# Optronik.net
KiCad netlist of a schematic drawn in EAGLE
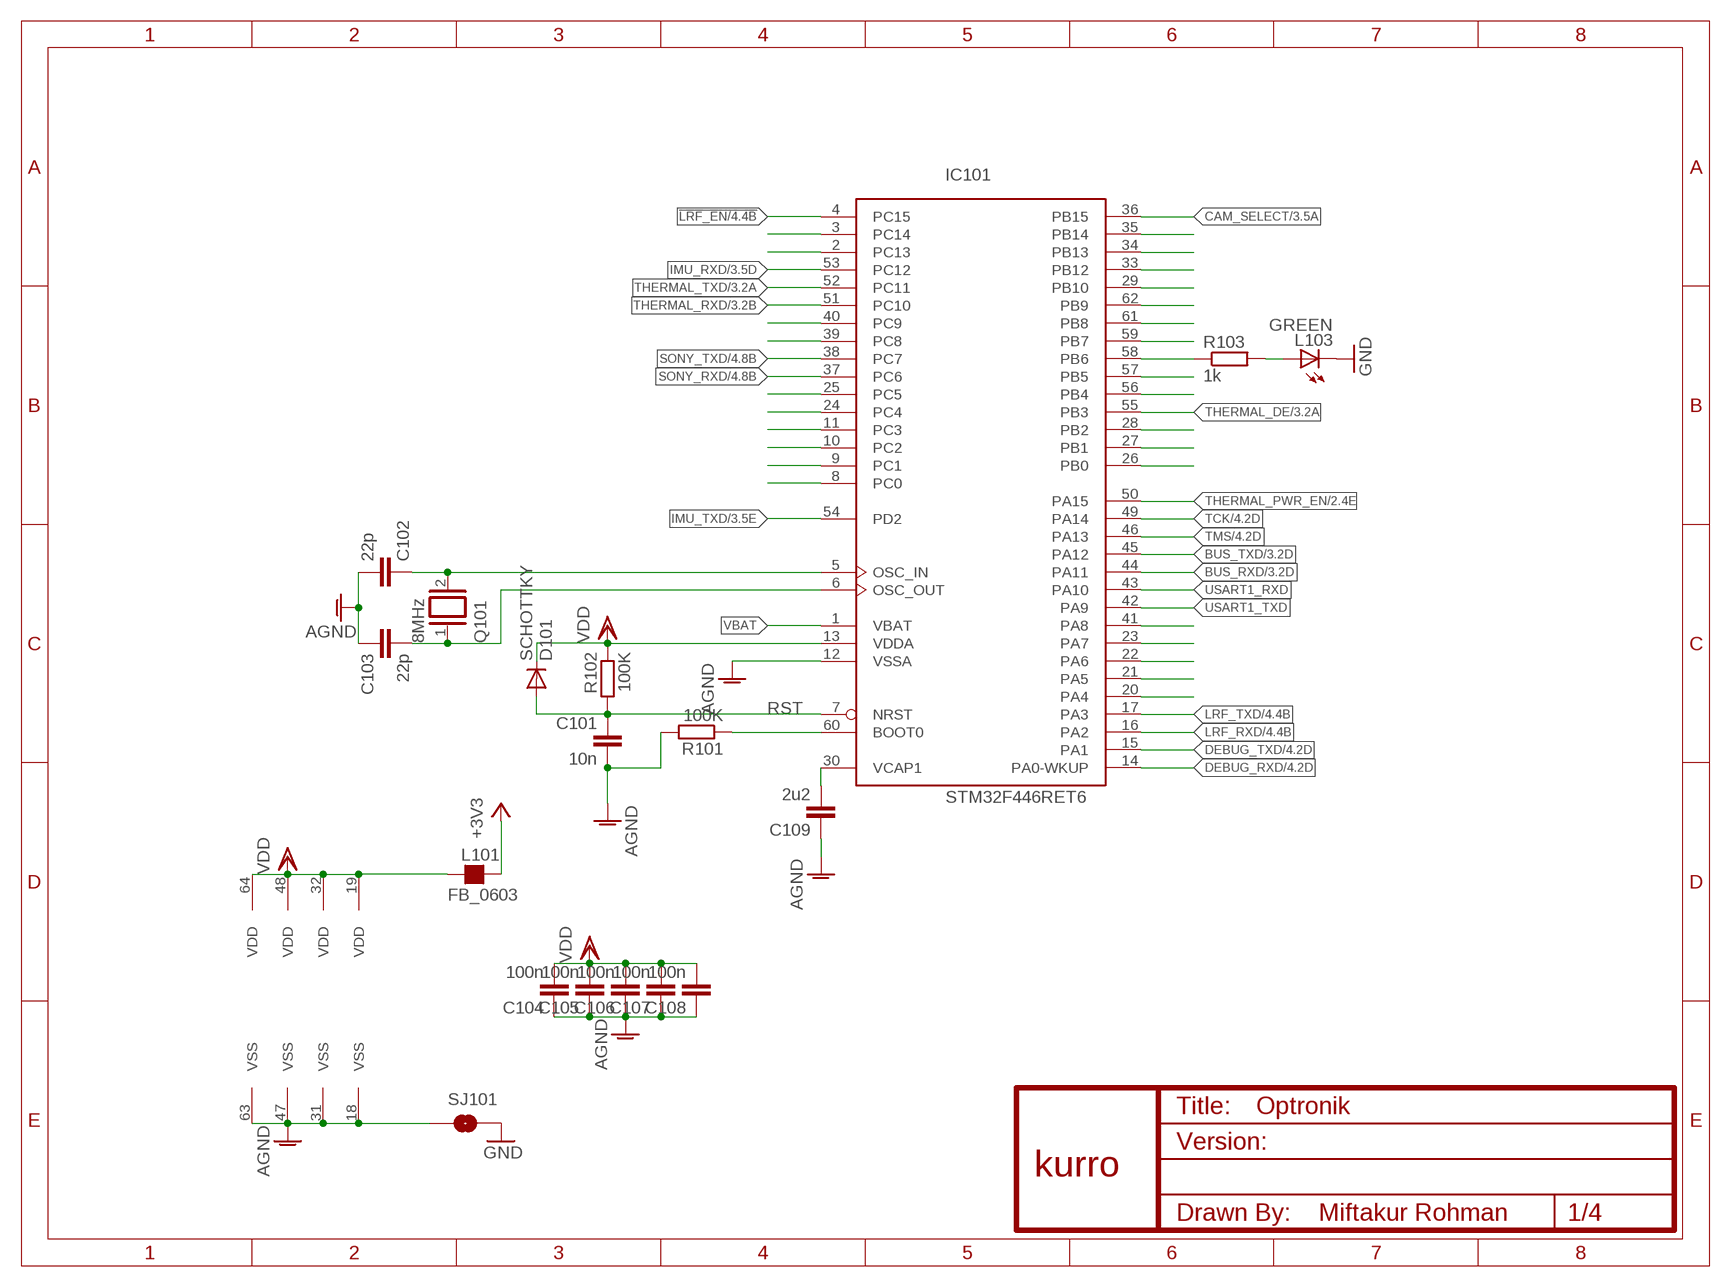
[diagram p0: schematic, sheet 1]
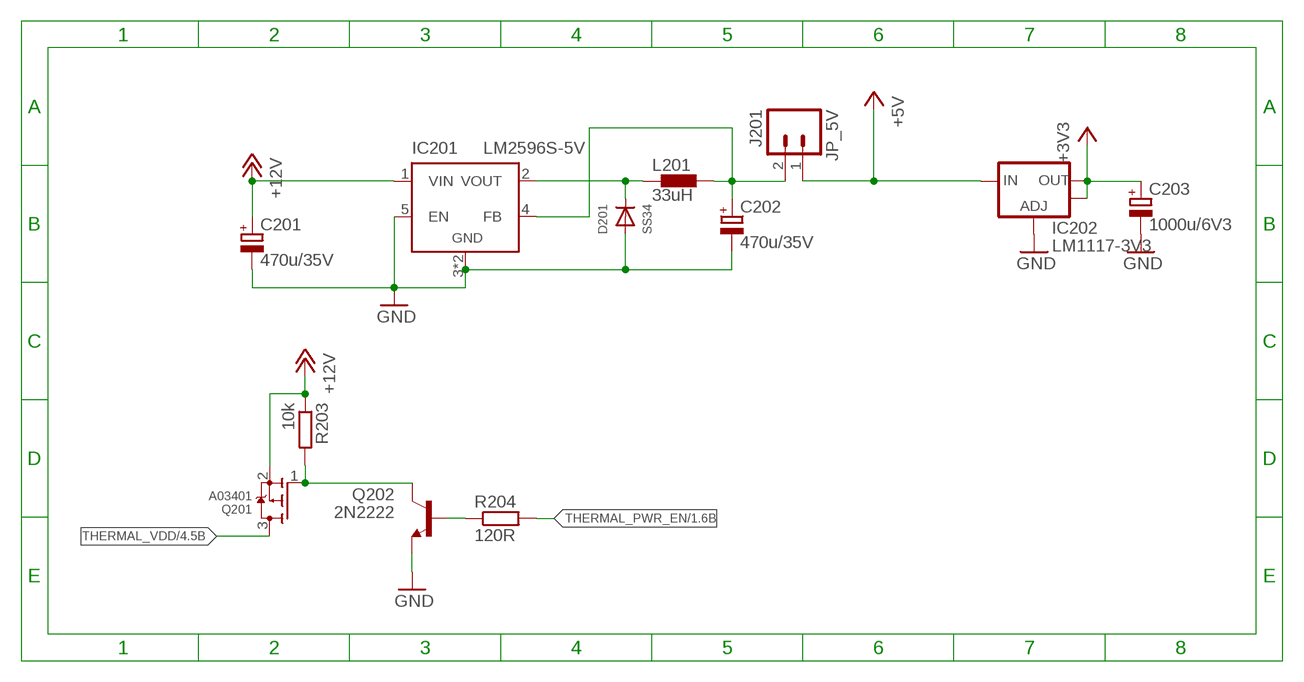
[diagram p1: schematic, sheet 2]
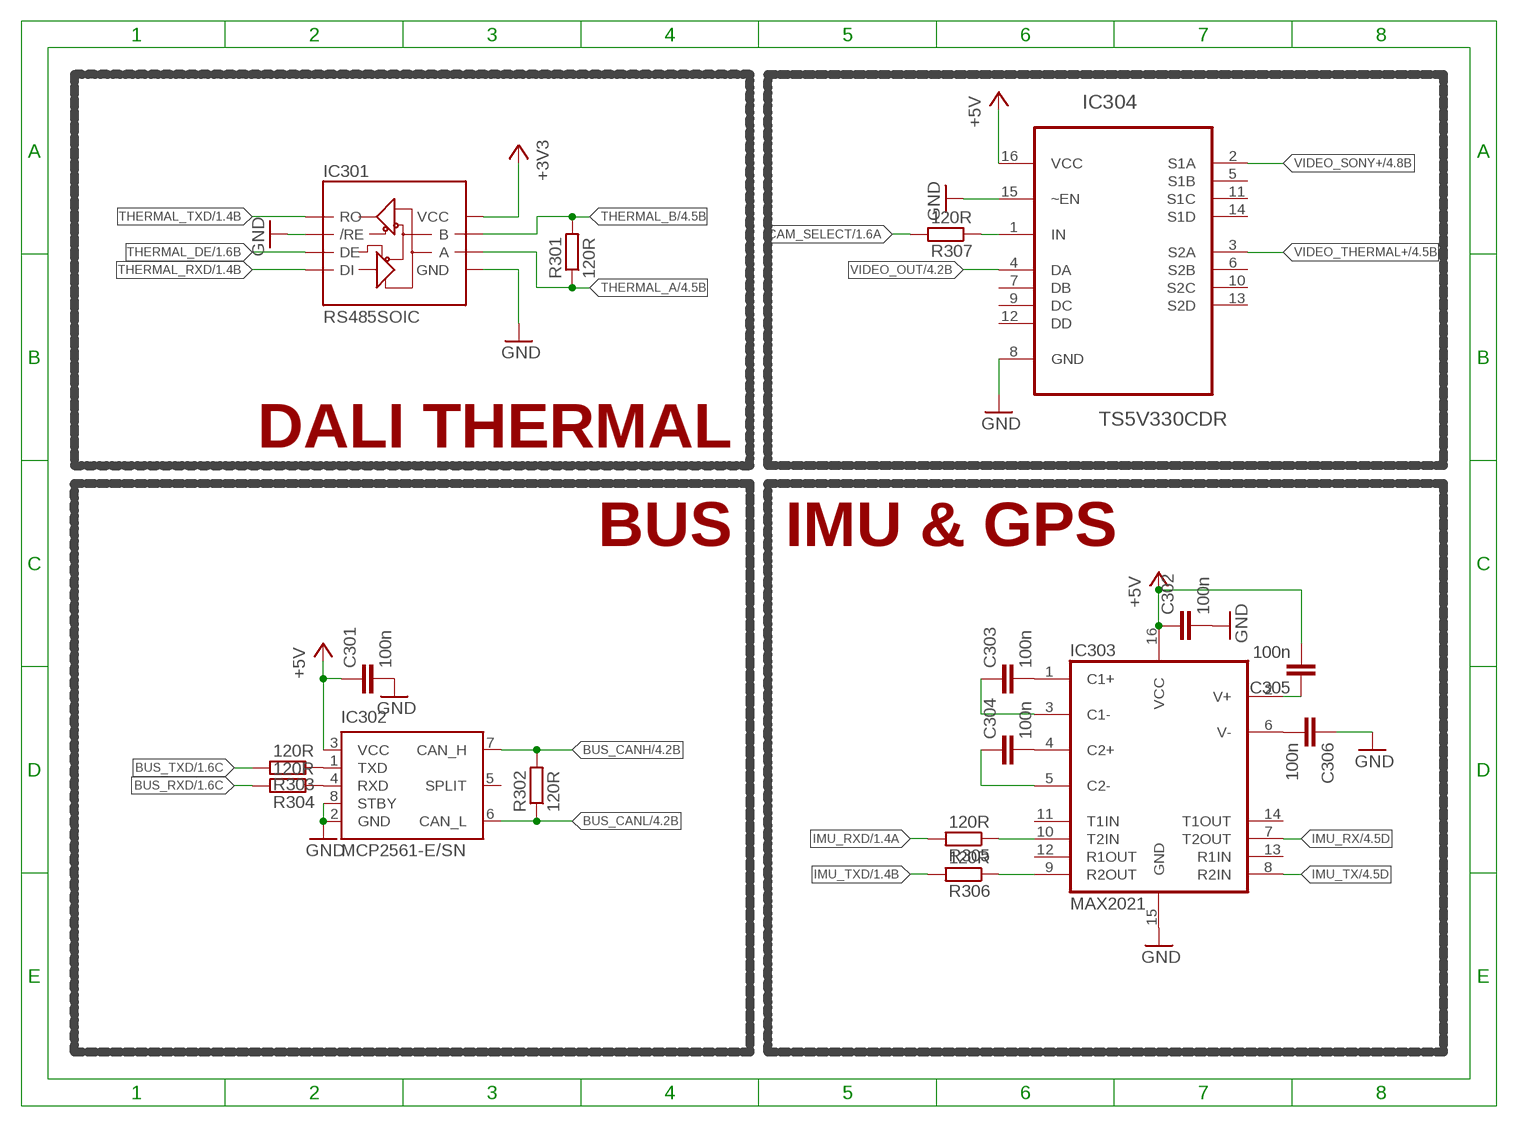
[diagram p2: schematic, sheet 3]
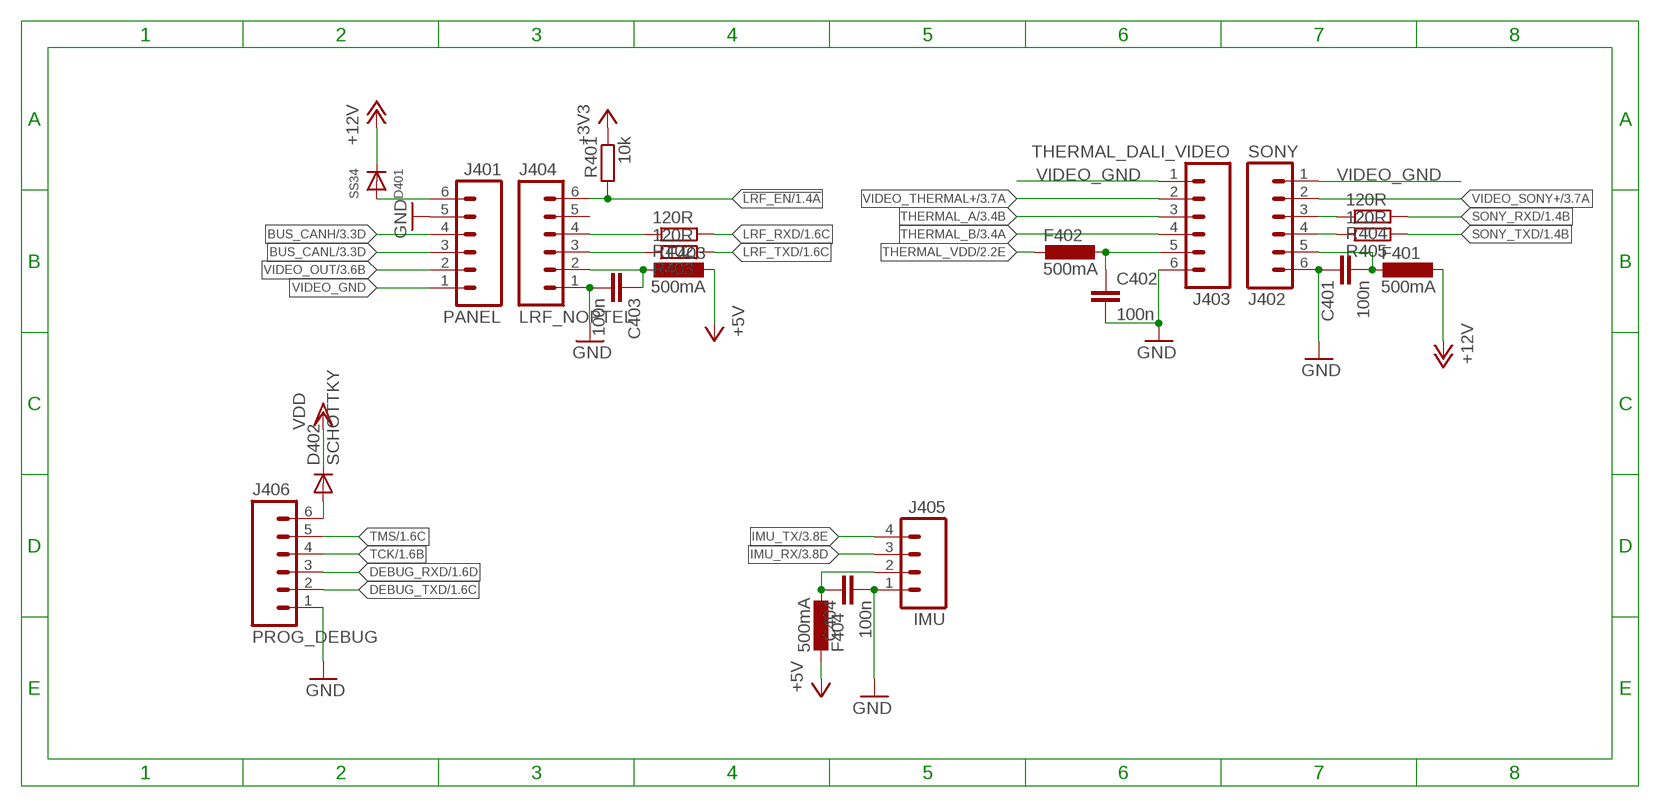
[diagram p3: schematic, sheet 4]

(export (version "E")
  (design (tool "Eeschema 10.0.6"))
  (components
    (comp (ref "C101")
      (value "10n")
      (footprint "eagle-import:C0603")
      (libsource (lib "eagle-import") (part "resistor_C-EUC0603"))
    )
    (comp (ref "C102")
      (value "22p")
      (footprint "eagle-import:C0603")
      (libsource (lib "eagle-import") (part "resistor_C-EUC0603"))
    )
    (comp (ref "C103")
      (value "22p")
      (footprint "eagle-import:C0603")
      (libsource (lib "eagle-import") (part "resistor_C-EUC0603"))
    )
    (comp (ref "C104")
      (value "100n")
      (footprint "eagle-import:C0603")
      (libsource (lib "eagle-import") (part "resistor_C-EUC0603"))
    )
    (comp (ref "C105")
      (value "100n")
      (footprint "eagle-import:C0603")
      (libsource (lib "eagle-import") (part "resistor_C-EUC0603"))
    )
    (comp (ref "C106")
      (value "100n")
      (footprint "eagle-import:C0603")
      (libsource (lib "eagle-import") (part "resistor_C-EUC0603"))
    )
    (comp (ref "C107")
      (value "100n")
      (footprint "eagle-import:C0603")
      (libsource (lib "eagle-import") (part "resistor_C-EUC0603"))
    )
    (comp (ref "C108")
      (value "100n")
      (footprint "eagle-import:C0603")
      (libsource (lib "eagle-import") (part "resistor_C-EUC0603"))
    )
    (comp (ref "C109")
      (value "2u2")
      (footprint "eagle-import:C0603")
      (libsource (lib "eagle-import") (part "resistor_C-EUC0603"))
    )
    (comp (ref "D101")
      (value "SCHOTTKY")
      (footprint "eagle-import:MICROMELF-W")
      (libsource (lib "eagle-import") (part "DIODE-MICROMELF-W"))
    )
    (comp (ref "IC101")
      (value "STM32F446RET6")
      (footprint "eagle-import:LQFP64")
      (libsource (lib "eagle-import") (part "STM32F401RTB"))
    )
    (comp (ref "L101")
      (value "FB_0603")
      (footprint "eagle-import:L0603")
      (libsource (lib "eagle-import") (part "FB_0603"))
    )
    (comp (ref "L103")
      (value "GREEN")
      (footprint "eagle-import:CHIP-LED0805")
      (libsource (lib "eagle-import") (part "LEDCHIP-LED0805"))
    )
    (comp (ref "Q101")
      (value "8MHz")
      (footprint "eagle-import:QS")
      (libsource (lib "eagle-import") (part "XTAL/S"))
    )
    (comp (ref "R101")
      (value "100K")
      (footprint "eagle-import:R0603")
      (libsource (lib "eagle-import") (part "resistor_R-EU_R0603"))
    )
    (comp (ref "R102")
      (value "100K")
      (footprint "eagle-import:R0603")
      (libsource (lib "eagle-import") (part "resistor_R-EU_R0603"))
    )
    (comp (ref "R103")
      (value "1k")
      (footprint "eagle-import:R0603")
      (libsource (lib "eagle-import") (part "resistor_R-EU_R0603"))
    )
    (comp (ref "SJ101")
      (value "SOLDERJUMPERTRACE")
      (footprint "eagle-import:SJ_2S-TRACE")
      (libsource (lib "eagle-import") (part "SOLDERJUMPERTRACE"))
    )
    (comp (ref "U$1")
      (value "KURRO_FOOTPRINT")
      (footprint "eagle-import:KURRO-LOGO")
      (libsource (lib "eagle-import") (part "KURRO_FOOTPRINT"))
    )
    (comp (ref "C201")
      (value "470u/35V")
      (footprint "eagle-import:153CLV-1012")
      (libsource (lib "eagle-import") (part "CPOL-EU153CLV-1012"))
    )
    (comp (ref "C202")
      (value "470u/35V")
      (footprint "eagle-import:153CLV-1012")
      (libsource (lib "eagle-import") (part "CPOL-EU153CLV-1012"))
    )
    (comp (ref "C203")
      (value "1000u/6V3")
      (footprint "eagle-import:153CLV-0810")
      (libsource (lib "eagle-import") (part "CPOL-EU153CLV-0810"))
    )
    (comp (ref "D201")
      (value "SS34")
      (footprint "eagle-import:SMADIODE")
      (libsource (lib "eagle-import") (part "DIODESMA"))
    )
    (comp (ref "IC201")
      (value "LM2596S-5V")
      (footprint "eagle-import:D2PAK")
      (libsource (lib "eagle-import") (part "LM2596S-ADJ"))
    )
    (comp (ref "IC202")
      (value "LM1117-3V3")
      (footprint "eagle-import:SOT223")
      (libsource (lib "eagle-import") (part "V_REG_LM1117SOT223"))
    )
    (comp (ref "J201")
      (value "JP_5V")
      (footprint "eagle-import:XH-2-VERT-SMD")
      (libsource (lib "eagle-import") (part "M02-XH-VERT-SMD"))
    )
    (comp (ref "L201")
      (value "33uH")
      (footprint "eagle-import:PA4342")
      (libsource (lib "eagle-import") (part "PA4342"))
    )
    (comp (ref "Q201")
      (value "A03401")
      (footprint "eagle-import:SOT23-W")
      (libsource (lib "eagle-import") (part "A03401-WIDE"))
    )
    (comp (ref "Q202")
      (value "2N2222")
      (footprint "eagle-import:SOT23")
      (libsource (lib "eagle-import") (part "2N2222-REFLOW"))
    )
    (comp (ref "R203")
      (value "10k")
      (footprint "eagle-import:R0603")
      (libsource (lib "eagle-import") (part "resistor_R-EU_R0603"))
    )
    (comp (ref "R204")
      (value "120R")
      (footprint "eagle-import:R0603")
      (libsource (lib "eagle-import") (part "resistor_R-EU_R0603"))
    )
    (comp (ref "C301")
      (value "100n")
      (footprint "eagle-import:C0603")
      (libsource (lib "eagle-import") (part "C-EUC0603"))
    )
    (comp (ref "C302")
      (value "100n")
      (footprint "eagle-import:C0603")
      (libsource (lib "eagle-import") (part "resistor_C-EUC0603"))
    )
    (comp (ref "C303")
      (value "100n")
      (footprint "eagle-import:C0603")
      (libsource (lib "eagle-import") (part "resistor_C-EUC0603"))
    )
    (comp (ref "C304")
      (value "100n")
      (footprint "eagle-import:C0603")
      (libsource (lib "eagle-import") (part "resistor_C-EUC0603"))
    )
    (comp (ref "C305")
      (value "100n")
      (footprint "eagle-import:C0603")
      (libsource (lib "eagle-import") (part "resistor_C-EUC0603"))
    )
    (comp (ref "C306")
      (value "100n")
      (footprint "eagle-import:C0603")
      (libsource (lib "eagle-import") (part "resistor_C-EUC0603"))
    )
    (comp (ref "IC301")
      (value "RS485SOIC")
      (footprint "eagle-import:SO08")
      (libsource (lib "eagle-import") (part "RS485SOIC"))
    )
    (comp (ref "IC302")
      (value "MCP2561-E/SN")
      (footprint "eagle-import:SOIC-8")
      (libsource (lib "eagle-import") (part "MCP2561-E/SN"))
    )
    (comp (ref "IC303")
      (value "MAX2021")
      (footprint "eagle-import:SO016")
      (libsource (lib "eagle-import") (part "MAX232SOIC16"))
    )
    (comp (ref "IC304")
      (value "TS5V330CDR")
      (footprint "eagle-import:SOIC127P600X175-16N")
      (libsource (lib "eagle-import") (part "TS5V330CDR"))
    )
    (comp (ref "R301")
      (value "120R")
      (footprint "eagle-import:R0603")
      (libsource (lib "eagle-import") (part "R-EU_R0603"))
    )
    (comp (ref "R302")
      (value "120R")
      (footprint "eagle-import:R0603")
      (libsource (lib "eagle-import") (part "R-EU_R0603"))
    )
    (comp (ref "R303")
      (value "120R")
      (footprint "eagle-import:R0603")
      (libsource (lib "eagle-import") (part "R-EU_R0603"))
    )
    (comp (ref "R304")
      (value "120R")
      (footprint "eagle-import:R0603")
      (libsource (lib "eagle-import") (part "R-EU_R0603"))
    )
    (comp (ref "R305")
      (value "120R")
      (footprint "eagle-import:R0603")
      (libsource (lib "eagle-import") (part "R-EU_R0603"))
    )
    (comp (ref "R306")
      (value "120R")
      (footprint "eagle-import:R0603")
      (libsource (lib "eagle-import") (part "R-EU_R0603"))
    )
    (comp (ref "R307")
      (value "120R")
      (footprint "eagle-import:R0603")
      (libsource (lib "eagle-import") (part "R-EU_R0603"))
    )
    (comp (ref "C401")
      (value "100n")
      (footprint "eagle-import:C0603")
      (libsource (lib "eagle-import") (part "resistor_C-EUC0603"))
    )
    (comp (ref "C402")
      (value "100n")
      (footprint "eagle-import:C0603")
      (libsource (lib "eagle-import") (part "resistor_C-EUC0603"))
    )
    (comp (ref "C403")
      (value "100n")
      (footprint "eagle-import:C0603")
      (libsource (lib "eagle-import") (part "resistor_C-EUC0603"))
    )
    (comp (ref "C404")
      (value "100n")
      (footprint "eagle-import:C0603")
      (libsource (lib "eagle-import") (part "resistor_C-EUC0603"))
    )
    (comp (ref "D401")
      (value "SS34")
      (footprint "eagle-import:SMADIODE")
      (libsource (lib "eagle-import") (part "DIODESMA"))
    )
    (comp (ref "D402")
      (value "SCHOTTKY")
      (footprint "eagle-import:MICROMELF-W")
      (libsource (lib "eagle-import") (part "DIODE-MICROMELF-W"))
    )
    (comp (ref "F401")
      (value "500mA")
      (footprint "eagle-import:L0805")
      (libsource (lib "eagle-import") (part "L-EUL0805"))
    )
    (comp (ref "F402")
      (value "500mA")
      (footprint "eagle-import:L0805")
      (libsource (lib "eagle-import") (part "L-EUL0805"))
    )
    (comp (ref "F403")
      (value "500mA")
      (footprint "eagle-import:L0805")
      (libsource (lib "eagle-import") (part "L-EUL0805"))
    )
    (comp (ref "F404")
      (value "500mA")
      (footprint "eagle-import:L0805")
      (libsource (lib "eagle-import") (part "L-EUL0805"))
    )
    (comp (ref "J401")
      (value "PANEL")
      (footprint "eagle-import:XH-6-RA")
      (libsource (lib "eagle-import") (part "M06-XH-RA"))
    )
    (comp (ref "J402")
      (value "SONY")
      (footprint "eagle-import:XH-6-RA")
      (libsource (lib "eagle-import") (part "M06-XH-RA"))
    )
    (comp (ref "J403")
      (value "THERMAL_DALI_VIDEO")
      (footprint "eagle-import:XH-6-RA")
      (libsource (lib "eagle-import") (part "M06-XH-RA"))
    )
    (comp (ref "J404")
      (value "LRF_NOPTEL")
      (footprint "eagle-import:XH-6-RA")
      (libsource (lib "eagle-import") (part "M06-XH-RA"))
    )
    (comp (ref "J405")
      (value "IMU")
      (footprint "eagle-import:XH-4-RA")
      (libsource (lib "eagle-import") (part "M04-XH-RA"))
    )
    (comp (ref "J406")
      (value "PROG_DEBUG")
      (footprint "eagle-import:XH-6-VERT")
      (libsource (lib "eagle-import") (part "M06-XH-VERT"))
    )
    (comp (ref "R401")
      (value "10k")
      (footprint "eagle-import:R0603")
      (libsource (lib "eagle-import") (part "resistor_R-EU_R0603"))
    )
    (comp (ref "R402")
      (value "120R")
      (footprint "eagle-import:R0603")
      (libsource (lib "eagle-import") (part "resistor_R-EU_R0603"))
    )
    (comp (ref "R403")
      (value "120R")
      (footprint "eagle-import:R0603")
      (libsource (lib "eagle-import") (part "resistor_R-EU_R0603"))
    )
    (comp (ref "R404")
      (value "120R")
      (footprint "eagle-import:R0603")
      (libsource (lib "eagle-import") (part "resistor_R-EU_R0603"))
    )
    (comp (ref "R405")
      (value "120R")
      (footprint "eagle-import:R0603")
      (libsource (lib "eagle-import") (part "resistor_R-EU_R0603"))
    )
  )
  (nets
    (net (code "1") (name "+3V3") (class "Default")
      (node (ref "C203") (pin "+") (pinfunction "+_+") (pintype "passive"))
      (node (ref "IC202") (pin "2") (pinfunction "OUT_2") (pintype "power_in"))
      (node (ref "IC202") (pin "4") (pinfunction "OUT_4") (pintype "power_in"))
      (node (ref "IC301") (pin "8") (pinfunction "VCC_8") (pintype "bidirectional"))
      (node (ref "L101") (pin "2") (pinfunction "2_2") (pintype "passive"))
      (node (ref "R401") (pin "1") (pinfunction "1_1") (pintype "passive"))
    )
    (net (code "2") (name "+5V") (class "Default")
      (node (ref "C301") (pin "1") (pinfunction "1_1") (pintype "passive"))
      (node (ref "C302") (pin "1") (pinfunction "1_1") (pintype "passive"))
      (node (ref "C305") (pin "2") (pinfunction "2_2") (pintype "passive"))
      (node (ref "F403") (pin "2") (pinfunction "2_2") (pintype "passive"))
      (node (ref "F404") (pin "2") (pinfunction "2_2") (pintype "passive"))
      (node (ref "IC202") (pin "3") (pinfunction "IN_3") (pintype "input"))
      (node (ref "IC302") (pin "3") (pinfunction "VCC_3") (pintype "bidirectional"))
      (node (ref "IC303") (pin "16") (pinfunction "VCC_16") (pintype "bidirectional"))
      (node (ref "IC304") (pin "16") (pinfunction "VCC_16") (pintype "power_in"))
      (node (ref "J201") (pin "1") (pinfunction "1_1") (pintype "passive"))
    )
    (net (code "3") (name "+12V") (class "Default")
      (node (ref "C201") (pin "+") (pinfunction "+_+") (pintype "passive"))
      (node (ref "D401") (pin "C") (pinfunction "C_C") (pintype "passive"))
      (node (ref "F401") (pin "1") (pinfunction "1_1") (pintype "passive"))
      (node (ref "IC201") (pin "1") (pinfunction "VIN_1") (pintype "power_in"))
      (node (ref "Q201") (pin "2") (pinfunction "S_2") (pintype "bidirectional"))
      (node (ref "R203") (pin "1") (pinfunction "1_1") (pintype "passive"))
    )
    (net (code "4") (name "AGND") (class "Default")
      (node (ref "C101") (pin "2") (pinfunction "2_2") (pintype "passive"))
      (node (ref "C102") (pin "2") (pinfunction "2_2") (pintype "passive"))
      (node (ref "C103") (pin "1") (pinfunction "1_1") (pintype "passive"))
      (node (ref "C104") (pin "1") (pinfunction "1_1") (pintype "passive"))
      (node (ref "C105") (pin "1") (pinfunction "1_1") (pintype "passive"))
      (node (ref "C106") (pin "1") (pinfunction "1_1") (pintype "passive"))
      (node (ref "C107") (pin "1") (pinfunction "1_1") (pintype "passive"))
      (node (ref "C108") (pin "1") (pinfunction "1_1") (pintype "passive"))
      (node (ref "C109") (pin "1") (pinfunction "1_1") (pintype "passive"))
      (node (ref "IC101") (pin "12") (pinfunction "VSSA_12") (pintype "power_in"))
      (node (ref "IC101") (pin "18") (pinfunction "VSS_18") (pintype "power_in"))
      (node (ref "IC101") (pin "31") (pinfunction "VSS_31") (pintype "power_in"))
      (node (ref "IC101") (pin "47") (pinfunction "VSS_47") (pintype "power_in"))
      (node (ref "IC101") (pin "63") (pinfunction "VSS_63") (pintype "power_in"))
      (node (ref "R101") (pin "2") (pinfunction "2_2") (pintype "passive"))
      (node (ref "SJ101") (pin "1") (pinfunction "1_1") (pintype "passive"))
    )
    (net (code "5") (name "BUS_CANH") (class "Default")
      (node (ref "IC302") (pin "7") (pinfunction "CAN_H_7") (pintype "bidirectional"))
      (node (ref "J401") (pin "4") (pinfunction "4_4") (pintype "passive"))
      (node (ref "R302") (pin "2") (pinfunction "2_2") (pintype "passive"))
    )
    (net (code "6") (name "BUS_CANL") (class "Default")
      (node (ref "IC302") (pin "6") (pinfunction "CAN_L_6") (pintype "bidirectional"))
      (node (ref "J401") (pin "3") (pinfunction "3_3") (pintype "passive"))
      (node (ref "R302") (pin "1") (pinfunction "1_1") (pintype "passive"))
    )
    (net (code "7") (name "BUS_RXD") (class "Default")
      (node (ref "IC101") (pin "44") (pinfunction "PA11_44") (pintype "bidirectional"))
      (node (ref "R304") (pin "2") (pinfunction "2_2") (pintype "passive"))
    )
    (net (code "8") (name "BUS_TXD") (class "Default")
      (node (ref "IC101") (pin "45") (pinfunction "PA12_45") (pintype "bidirectional"))
      (node (ref "R303") (pin "2") (pinfunction "2_2") (pintype "passive"))
    )
    (net (code "9") (name "CAM_SELECT") (class "Default")
      (node (ref "IC101") (pin "36") (pinfunction "PB15_36") (pintype "bidirectional"))
      (node (ref "R307") (pin "2") (pinfunction "2_2") (pintype "passive"))
    )
    (net (code "10") (name "DEBUG_RXD") (class "Default")
      (node (ref "IC101") (pin "14") (pinfunction "PA0-WKUP_14") (pintype "bidirectional"))
      (node (ref "J406") (pin "3") (pinfunction "3_3") (pintype "passive"))
    )
    (net (code "11") (name "DEBUG_TXD") (class "Default")
      (node (ref "IC101") (pin "15") (pinfunction "PA1_15") (pintype "bidirectional"))
      (node (ref "J406") (pin "2") (pinfunction "2_2") (pintype "passive"))
    )
    (net (code "12") (name "GND") (class "Default")
      (node (ref "C201") (pin "-") (pinfunction "-_-") (pintype "passive"))
      (node (ref "C202") (pin "-") (pinfunction "-_-") (pintype "passive"))
      (node (ref "C203") (pin "-") (pinfunction "-_-") (pintype "passive"))
      (node (ref "C301") (pin "2") (pinfunction "2_2") (pintype "passive"))
      (node (ref "C302") (pin "2") (pinfunction "2_2") (pintype "passive"))
      (node (ref "C306") (pin "1") (pinfunction "1_1") (pintype "passive"))
      (node (ref "C401") (pin "1") (pinfunction "1_1") (pintype "passive"))
      (node (ref "C402") (pin "2") (pinfunction "2_2") (pintype "passive"))
      (node (ref "C403") (pin "2") (pinfunction "2_2") (pintype "passive"))
      (node (ref "C404") (pin "2") (pinfunction "2_2") (pintype "passive"))
      (node (ref "D201") (pin "A") (pinfunction "A_A") (pintype "passive"))
      (node (ref "IC201") (pin "3") (pinfunction "GND_3") (pintype "passive"))
      (node (ref "IC201") (pin "5") (pinfunction "EN_5") (pintype "input"))
      (node (ref "IC201") (pin "6") (pinfunction "GND_6") (pintype "passive"))
      (node (ref "IC202") (pin "1") (pinfunction "ADJ_1") (pintype "input"))
      (node (ref "IC301") (pin "2") (pinfunction "/RE_2") (pintype "bidirectional"))
      (node (ref "IC301") (pin "5") (pinfunction "GND_5") (pintype "bidirectional"))
      (node (ref "IC302") (pin "2") (pinfunction "GND_2") (pintype "bidirectional"))
      (node (ref "IC302") (pin "8") (pinfunction "STBY_8") (pintype "bidirectional"))
      (node (ref "IC303") (pin "15") (pinfunction "GND_15") (pintype "bidirectional"))
      (node (ref "IC304") (pin "15") (pinfunction "~{EN}_15") (pintype "input"))
      (node (ref "IC304") (pin "8") (pinfunction "GND_8") (pintype "passive"))
      (node (ref "J401") (pin "5") (pinfunction "5_5") (pintype "passive"))
      (node (ref "J402") (pin "6") (pinfunction "6_6") (pintype "passive"))
      (node (ref "J403") (pin "6") (pinfunction "6_6") (pintype "passive"))
      (node (ref "J404") (pin "1") (pinfunction "1_1") (pintype "passive"))
      (node (ref "J405") (pin "1") (pinfunction "1_1") (pintype "passive"))
      (node (ref "J406") (pin "1") (pinfunction "1_1") (pintype "passive"))
      (node (ref "L103") (pin "C") (pinfunction "C_C") (pintype "passive"))
      (node (ref "Q202") (pin "2") (pinfunction "E_2") (pintype "passive"))
      (node (ref "SJ101") (pin "2") (pinfunction "2_2") (pintype "passive"))
    )
    (net (code "13") (name "IMU_RX") (class "Default")
      (node (ref "IC303") (pin "7") (pinfunction "T2OUT_7") (pintype "output"))
      (node (ref "J405") (pin "3") (pinfunction "3_3") (pintype "passive"))
    )
    (net (code "14") (name "IMU_RXD") (class "Default")
      (node (ref "IC101") (pin "53") (pinfunction "PC12_53") (pintype "bidirectional"))
      (node (ref "R305") (pin "2") (pinfunction "2_2") (pintype "passive"))
    )
    (net (code "15") (name "IMU_TX") (class "Default")
      (node (ref "IC303") (pin "8") (pinfunction "R2IN_8") (pintype "input"))
      (node (ref "J405") (pin "4") (pinfunction "4_4") (pintype "passive"))
    )
    (net (code "16") (name "IMU_TXD") (class "Default")
      (node (ref "IC101") (pin "54") (pinfunction "PD2_54") (pintype "bidirectional"))
      (node (ref "R306") (pin "2") (pinfunction "2_2") (pintype "passive"))
    )
    (net (code "17") (name "LRF_RXD") (class "Default")
      (node (ref "IC101") (pin "16") (pinfunction "PA2_16") (pintype "bidirectional"))
      (node (ref "R402") (pin "2") (pinfunction "2_2") (pintype "passive"))
    )
    (net (code "18") (name "LRF_TXD") (class "Default")
      (node (ref "IC101") (pin "17") (pinfunction "PA3_17") (pintype "bidirectional"))
      (node (ref "R403") (pin "2") (pinfunction "2_2") (pintype "passive"))
    )
    (net (code "19") (name "Net-(C401-Pad2)") (class "Default")
      (node (ref "C401") (pin "2") (pinfunction "2_2") (pintype "passive"))
      (node (ref "F401") (pin "2") (pinfunction "2_2") (pintype "passive"))
      (node (ref "J402") (pin "5") (pinfunction "5_5") (pintype "passive"))
    )
    (net (code "20") (name "Net-(C402-Pad1)") (class "Default")
      (node (ref "C402") (pin "1") (pinfunction "1_1") (pintype "passive"))
      (node (ref "F402") (pin "1") (pinfunction "1_1") (pintype "passive"))
      (node (ref "J403") (pin "5") (pinfunction "5_5") (pintype "passive"))
    )
    (net (code "21") (name "Net-(C403-Pad1)") (class "Default")
      (node (ref "C403") (pin "1") (pinfunction "1_1") (pintype "passive"))
      (node (ref "F403") (pin "1") (pinfunction "1_1") (pintype "passive"))
      (node (ref "J404") (pin "2") (pinfunction "2_2") (pintype "passive"))
    )
    (net (code "22") (name "Net-(C404-Pad1)") (class "Default")
      (node (ref "C404") (pin "1") (pinfunction "1_1") (pintype "passive"))
      (node (ref "F404") (pin "1") (pinfunction "1_1") (pintype "passive"))
      (node (ref "J405") (pin "2") (pinfunction "2_2") (pintype "passive"))
    )
    (net (code "23") (name "Net-(D401-PadA)") (class "Default")
      (node (ref "D401") (pin "A") (pinfunction "A_A") (pintype "passive"))
      (node (ref "J401") (pin "6") (pinfunction "6_6") (pintype "passive"))
    )
    (net (code "24") (name "Net-(D402-PadA)") (class "Default")
      (node (ref "D402") (pin "A") (pinfunction "A_A") (pintype "passive"))
      (node (ref "J406") (pin "6") (pinfunction "6_6") (pintype "passive"))
    )
    (net (code "25") (name "Net-(IC101A-BOOT0)") (class "Default")
      (node (ref "IC101") (pin "60") (pinfunction "BOOT0_60") (pintype "input"))
      (node (ref "R101") (pin "1") (pinfunction "1_1") (pintype "passive"))
    )
    (net (code "26") (name "Net-(IC101A-OSC_IN)") (class "Default")
      (node (ref "C102") (pin "1") (pinfunction "1_1") (pintype "passive"))
      (node (ref "IC101") (pin "5") (pinfunction "OSC_IN_5") (pintype "bidirectional"))
      (node (ref "Q101") (pin "2") (pinfunction "2_2") (pintype "passive"))
    )
    (net (code "27") (name "Net-(IC101A-OSC_OUT)") (class "Default")
      (node (ref "C103") (pin "2") (pinfunction "2_2") (pintype "passive"))
      (node (ref "IC101") (pin "6") (pinfunction "OSC_OUT_6") (pintype "bidirectional"))
      (node (ref "Q101") (pin "1") (pinfunction "1_1") (pintype "passive"))
    )
    (net (code "28") (name "Net-(IC101A-PB6)") (class "Default")
      (node (ref "IC101") (pin "58") (pinfunction "PB6_58") (pintype "bidirectional"))
      (node (ref "R103") (pin "1") (pinfunction "1_1") (pintype "passive"))
    )
    (net (code "29") (name "Net-(IC101A-VCAP1)") (class "Default")
      (node (ref "C109") (pin "2") (pinfunction "2_2") (pintype "passive"))
      (node (ref "IC101") (pin "30") (pinfunction "VCAP1_30") (pintype "power_in"))
    )
    (net (code "30") (name "Net-(IC201-FB)") (class "Default")
      (node (ref "C202") (pin "+") (pinfunction "+_+") (pintype "passive"))
      (node (ref "IC201") (pin "4") (pinfunction "FB_4") (pintype "input"))
      (node (ref "J201") (pin "2") (pinfunction "2_2") (pintype "passive"))
      (node (ref "L201") (pin "P$2") (pinfunction "2_P$2") (pintype "passive"))
    )
    (net (code "31") (name "Net-(IC201-VOUT)") (class "Default")
      (node (ref "D201") (pin "C") (pinfunction "C_C") (pintype "passive"))
      (node (ref "IC201") (pin "2") (pinfunction "VOUT_2") (pintype "output"))
      (node (ref "L201") (pin "P$1") (pinfunction "1_P$1") (pintype "passive"))
    )
    (net (code "32") (name "Net-(IC302-RXD)") (class "Default")
      (node (ref "IC302") (pin "4") (pinfunction "RXD_4") (pintype "bidirectional"))
      (node (ref "R304") (pin "1") (pinfunction "1_1") (pintype "passive"))
    )
    (net (code "33") (name "Net-(IC302-TXD)") (class "Default")
      (node (ref "IC302") (pin "1") (pinfunction "TXD_1") (pintype "bidirectional"))
      (node (ref "R303") (pin "1") (pinfunction "1_1") (pintype "passive"))
    )
    (net (code "34") (name "Net-(IC303-C1+)") (class "Default")
      (node (ref "C303") (pin "2") (pinfunction "2_2") (pintype "passive"))
      (node (ref "IC303") (pin "1") (pinfunction "C1+_1") (pintype "bidirectional"))
    )
    (net (code "35") (name "Net-(IC303-C1-)") (class "Default")
      (node (ref "C303") (pin "1") (pinfunction "1_1") (pintype "passive"))
      (node (ref "IC303") (pin "3") (pinfunction "C1-_3") (pintype "bidirectional"))
    )
    (net (code "36") (name "Net-(IC303-C2+)") (class "Default")
      (node (ref "C304") (pin "2") (pinfunction "2_2") (pintype "passive"))
      (node (ref "IC303") (pin "4") (pinfunction "C2+_4") (pintype "bidirectional"))
    )
    (net (code "37") (name "Net-(IC303-C2-)") (class "Default")
      (node (ref "C304") (pin "1") (pinfunction "1_1") (pintype "passive"))
      (node (ref "IC303") (pin "5") (pinfunction "C2-_5") (pintype "bidirectional"))
    )
    (net (code "38") (name "Net-(IC303-R2OUT)") (class "Default")
      (node (ref "IC303") (pin "9") (pinfunction "R2OUT_9") (pintype "output"))
      (node (ref "R306") (pin "1") (pinfunction "1_1") (pintype "passive"))
    )
    (net (code "39") (name "Net-(IC303-T2IN)") (class "Default")
      (node (ref "IC303") (pin "10") (pinfunction "T2IN_10") (pintype "input"))
      (node (ref "R305") (pin "1") (pinfunction "1_1") (pintype "passive"))
    )
    (net (code "40") (name "Net-(IC303-V+)") (class "Default")
      (node (ref "C305") (pin "1") (pinfunction "1_1") (pintype "passive"))
      (node (ref "IC303") (pin "2") (pinfunction "V+_2") (pintype "bidirectional"))
    )
    (net (code "41") (name "Net-(IC303-V-)") (class "Default")
      (node (ref "C306") (pin "2") (pinfunction "2_2") (pintype "passive"))
      (node (ref "IC303") (pin "6") (pinfunction "V-_6") (pintype "bidirectional"))
    )
    (net (code "42") (name "Net-(IC304-IN)") (class "Default")
      (node (ref "IC304") (pin "1") (pinfunction "IN_1") (pintype "input"))
      (node (ref "R307") (pin "1") (pinfunction "1_1") (pintype "passive"))
    )
    (net (code "43") (name "Net-(J402-Pad3)") (class "Default")
      (node (ref "J402") (pin "3") (pinfunction "3_3") (pintype "passive"))
      (node (ref "R404") (pin "1") (pinfunction "1_1") (pintype "passive"))
    )
    (net (code "44") (name "Net-(J402-Pad4)") (class "Default")
      (node (ref "J402") (pin "4") (pinfunction "4_4") (pintype "passive"))
      (node (ref "R405") (pin "1") (pinfunction "1_1") (pintype "passive"))
    )
    (net (code "45") (name "Net-(J404-Pad3)") (class "Default")
      (node (ref "J404") (pin "3") (pinfunction "3_3") (pintype "passive"))
      (node (ref "R403") (pin "1") (pinfunction "1_1") (pintype "passive"))
    )
    (net (code "46") (name "Net-(J404-Pad4)") (class "Default")
      (node (ref "J404") (pin "4") (pinfunction "4_4") (pintype "passive"))
      (node (ref "R402") (pin "1") (pinfunction "1_1") (pintype "passive"))
    )
    (net (code "47") (name "Net-(L103-PadA)") (class "Default")
      (node (ref "L103") (pin "A") (pinfunction "A_A") (pintype "passive"))
      (node (ref "R103") (pin "2") (pinfunction "2_2") (pintype "passive"))
    )
    (net (code "48") (name "Net-(Q201-G)") (class "Default")
      (node (ref "Q201") (pin "1") (pinfunction "G_1") (pintype "bidirectional"))
      (node (ref "Q202") (pin "3") (pinfunction "C_3") (pintype "passive"))
      (node (ref "R203") (pin "2") (pinfunction "2_2") (pintype "passive"))
    )
    (net (code "49") (name "Net-(Q202-B)") (class "Default")
      (node (ref "Q202") (pin "1") (pinfunction "B_1") (pintype "passive"))
      (node (ref "R204") (pin "1") (pinfunction "1_1") (pintype "passive"))
    )
    (net (code "50") (name "RST") (class "Default")
      (node (ref "C101") (pin "1") (pinfunction "1_1") (pintype "passive"))
      (node (ref "D101") (pin "A") (pinfunction "A_A") (pintype "passive"))
      (node (ref "IC101") (pin "7") (pinfunction "NRST_7") (pintype "bidirectional"))
      (node (ref "R102") (pin "2") (pinfunction "2_2") (pintype "passive"))
    )
    (net (code "51") (name "SONY_RXD") (class "Default")
      (node (ref "IC101") (pin "37") (pinfunction "PC6_37") (pintype "bidirectional"))
      (node (ref "R404") (pin "2") (pinfunction "2_2") (pintype "passive"))
    )
    (net (code "52") (name "SONY_TXD") (class "Default")
      (node (ref "IC101") (pin "38") (pinfunction "PC7_38") (pintype "bidirectional"))
      (node (ref "R405") (pin "2") (pinfunction "2_2") (pintype "passive"))
    )
    (net (code "53") (name "TCK") (class "Default")
      (node (ref "IC101") (pin "49") (pinfunction "PA14_49") (pintype "bidirectional"))
      (node (ref "J406") (pin "4") (pinfunction "4_4") (pintype "passive"))
    )
    (net (code "54") (name "THERMAL_A") (class "Default")
      (node (ref "IC301") (pin "6") (pinfunction "A_6") (pintype "bidirectional"))
      (node (ref "J403") (pin "3") (pinfunction "3_3") (pintype "passive"))
      (node (ref "R301") (pin "1") (pinfunction "1_1") (pintype "passive"))
    )
    (net (code "55") (name "THERMAL_B") (class "Default")
      (node (ref "IC301") (pin "7") (pinfunction "B_7") (pintype "bidirectional"))
      (node (ref "J403") (pin "4") (pinfunction "4_4") (pintype "passive"))
      (node (ref "R301") (pin "2") (pinfunction "2_2") (pintype "passive"))
    )
    (net (code "56") (name "THERMAL_DE") (class "Default")
      (node (ref "IC101") (pin "55") (pinfunction "PB3_55") (pintype "bidirectional"))
      (node (ref "IC301") (pin "3") (pinfunction "DE_3") (pintype "bidirectional"))
    )
    (net (code "57") (name "THERMAL_PWR_EN") (class "Default")
      (node (ref "IC101") (pin "50") (pinfunction "PA15_50") (pintype "bidirectional"))
      (node (ref "R204") (pin "2") (pinfunction "2_2") (pintype "passive"))
    )
    (net (code "58") (name "THERMAL_RXD") (class "Default")
      (node (ref "IC101") (pin "51") (pinfunction "PC10_51") (pintype "bidirectional"))
      (node (ref "IC301") (pin "4") (pinfunction "DI_4") (pintype "bidirectional"))
    )
    (net (code "59") (name "THERMAL_TXD") (class "Default")
      (node (ref "IC101") (pin "52") (pinfunction "PC11_52") (pintype "bidirectional"))
      (node (ref "IC301") (pin "1") (pinfunction "RO_1") (pintype "bidirectional"))
    )
    (net (code "60") (name "THERMAL_VDD") (class "Default")
      (node (ref "F402") (pin "2") (pinfunction "2_2") (pintype "passive"))
      (node (ref "Q201") (pin "3") (pinfunction "D_3") (pintype "bidirectional"))
    )
    (net (code "61") (name "TMS") (class "Default")
      (node (ref "IC101") (pin "46") (pinfunction "PA13_46") (pintype "bidirectional"))
      (node (ref "J406") (pin "5") (pinfunction "5_5") (pintype "passive"))
    )
    (net (code "62") (name "USART1_RXD") (class "Default")
      (node (ref "IC101") (pin "43") (pinfunction "PA10_43") (pintype "bidirectional"))
    )
    (net (code "63") (name "USART1_TXD") (class "Default")
      (node (ref "IC101") (pin "42") (pinfunction "PA9_42") (pintype "bidirectional"))
    )
    (net (code "64") (name "VBAT") (class "Default")
      (node (ref "IC101") (pin "1") (pinfunction "VBAT_1") (pintype "power_in"))
    )
    (net (code "65") (name "VDD") (class "Default")
      (node (ref "C104") (pin "2") (pinfunction "2_2") (pintype "passive"))
      (node (ref "C105") (pin "2") (pinfunction "2_2") (pintype "passive"))
      (node (ref "C106") (pin "2") (pinfunction "2_2") (pintype "passive"))
      (node (ref "C107") (pin "2") (pinfunction "2_2") (pintype "passive"))
      (node (ref "C108") (pin "2") (pinfunction "2_2") (pintype "passive"))
      (node (ref "D101") (pin "C") (pinfunction "C_C") (pintype "passive"))
      (node (ref "D402") (pin "C") (pinfunction "C_C") (pintype "passive"))
      (node (ref "IC101") (pin "13") (pinfunction "VDDA_13") (pintype "power_in"))
      (node (ref "IC101") (pin "19") (pinfunction "VDD_19") (pintype "power_in"))
      (node (ref "IC101") (pin "32") (pinfunction "VDD_32") (pintype "power_in"))
      (node (ref "IC101") (pin "48") (pinfunction "VDD_48") (pintype "power_in"))
      (node (ref "IC101") (pin "64") (pinfunction "VDD_64") (pintype "power_in"))
      (node (ref "L101") (pin "1") (pinfunction "1_1") (pintype "passive"))
      (node (ref "R102") (pin "1") (pinfunction "1_1") (pintype "passive"))
    )
    (net (code "66") (name "VIDEO_GND") (class "Default")
      (node (ref "J401") (pin "1") (pinfunction "1_1") (pintype "passive"))
      (node (ref "J402") (pin "1") (pinfunction "1_1") (pintype "passive"))
      (node (ref "J403") (pin "1") (pinfunction "1_1") (pintype "passive"))
    )
    (net (code "67") (name "VIDEO_OUT") (class "Default")
      (node (ref "IC304") (pin "4") (pinfunction "DA_4") (pintype "bidirectional"))
      (node (ref "J401") (pin "2") (pinfunction "2_2") (pintype "passive"))
    )
    (net (code "68") (name "VIDEO_SONY+") (class "Default")
      (node (ref "IC304") (pin "2") (pinfunction "S1A_2") (pintype "bidirectional"))
      (node (ref "J402") (pin "2") (pinfunction "2_2") (pintype "passive"))
    )
    (net (code "69") (name "VIDEO_THERMAL+") (class "Default")
      (node (ref "IC304") (pin "3") (pinfunction "S2A_3") (pintype "bidirectional"))
      (node (ref "J403") (pin "2") (pinfunction "2_2") (pintype "passive"))
    )
    (net (code "70") (name "unconnected-(IC101A-PA4-Pad20)") (class "Default")
      (node (ref "IC101") (pin "20") (pinfunction "PA4_20") (pintype "bidirectional"))
    )
    (net (code "71") (name "unconnected-(IC101A-PA5-Pad21)") (class "Default")
      (node (ref "IC101") (pin "21") (pinfunction "PA5_21") (pintype "bidirectional"))
    )
    (net (code "72") (name "unconnected-(IC101A-PA6-Pad22)") (class "Default")
      (node (ref "IC101") (pin "22") (pinfunction "PA6_22") (pintype "bidirectional"))
    )
    (net (code "73") (name "unconnected-(IC101A-PA7-Pad23)") (class "Default")
      (node (ref "IC101") (pin "23") (pinfunction "PA7_23") (pintype "bidirectional"))
    )
    (net (code "74") (name "unconnected-(IC101A-PA8-Pad41)") (class "Default")
      (node (ref "IC101") (pin "41") (pinfunction "PA8_41") (pintype "bidirectional"))
    )
    (net (code "75") (name "unconnected-(IC101A-PB0-Pad26)") (class "Default")
      (node (ref "IC101") (pin "26") (pinfunction "PB0_26") (pintype "bidirectional"))
    )
    (net (code "76") (name "unconnected-(IC101A-PB1-Pad27)") (class "Default")
      (node (ref "IC101") (pin "27") (pinfunction "PB1_27") (pintype "bidirectional"))
    )
    (net (code "77") (name "unconnected-(IC101A-PB2-Pad28)") (class "Default")
      (node (ref "IC101") (pin "28") (pinfunction "PB2_28") (pintype "bidirectional"))
    )
    (net (code "78") (name "unconnected-(IC101A-PB4-Pad56)") (class "Default")
      (node (ref "IC101") (pin "56") (pinfunction "PB4_56") (pintype "bidirectional"))
    )
    (net (code "79") (name "unconnected-(IC101A-PB5-Pad57)") (class "Default")
      (node (ref "IC101") (pin "57") (pinfunction "PB5_57") (pintype "bidirectional"))
    )
    (net (code "80") (name "unconnected-(IC101A-PB7-Pad59)") (class "Default")
      (node (ref "IC101") (pin "59") (pinfunction "PB7_59") (pintype "bidirectional"))
    )
    (net (code "81") (name "unconnected-(IC101A-PB8-Pad61)") (class "Default")
      (node (ref "IC101") (pin "61") (pinfunction "PB8_61") (pintype "bidirectional"))
    )
    (net (code "82") (name "unconnected-(IC101A-PB9-Pad62)") (class "Default")
      (node (ref "IC101") (pin "62") (pinfunction "PB9_62") (pintype "bidirectional"))
    )
    (net (code "83") (name "unconnected-(IC101A-PB10-Pad29)") (class "Default")
      (node (ref "IC101") (pin "29") (pinfunction "PB10_29") (pintype "bidirectional"))
    )
    (net (code "84") (name "unconnected-(IC101A-PB12-Pad33)") (class "Default")
      (node (ref "IC101") (pin "33") (pinfunction "PB12_33") (pintype "bidirectional"))
    )
    (net (code "85") (name "unconnected-(IC101A-PB13-Pad34)") (class "Default")
      (node (ref "IC101") (pin "34") (pinfunction "PB13_34") (pintype "bidirectional"))
    )
    (net (code "86") (name "unconnected-(IC101A-PB14-Pad35)") (class "Default")
      (node (ref "IC101") (pin "35") (pinfunction "PB14_35") (pintype "bidirectional"))
    )
    (net (code "87") (name "unconnected-(IC101A-PC0-Pad8)") (class "Default")
      (node (ref "IC101") (pin "8") (pinfunction "PC0_8") (pintype "bidirectional"))
    )
    (net (code "88") (name "unconnected-(IC101A-PC1-Pad9)") (class "Default")
      (node (ref "IC101") (pin "9") (pinfunction "PC1_9") (pintype "bidirectional"))
    )
    (net (code "89") (name "unconnected-(IC101A-PC2-Pad10)") (class "Default")
      (node (ref "IC101") (pin "10") (pinfunction "PC2_10") (pintype "bidirectional"))
    )
    (net (code "90") (name "unconnected-(IC101A-PC3-Pad11)") (class "Default")
      (node (ref "IC101") (pin "11") (pinfunction "PC3_11") (pintype "bidirectional"))
    )
    (net (code "91") (name "unconnected-(IC101A-PC4-Pad24)") (class "Default")
      (node (ref "IC101") (pin "24") (pinfunction "PC4_24") (pintype "bidirectional"))
    )
    (net (code "92") (name "unconnected-(IC101A-PC5-Pad25)") (class "Default")
      (node (ref "IC101") (pin "25") (pinfunction "PC5_25") (pintype "bidirectional"))
    )
    (net (code "93") (name "unconnected-(IC101A-PC8-Pad39)") (class "Default")
      (node (ref "IC101") (pin "39") (pinfunction "PC8_39") (pintype "bidirectional"))
    )
    (net (code "94") (name "unconnected-(IC101A-PC9-Pad40)") (class "Default")
      (node (ref "IC101") (pin "40") (pinfunction "PC9_40") (pintype "bidirectional"))
    )
    (net (code "95") (name "unconnected-(IC101A-PC13-Pad2)") (class "Default")
      (node (ref "IC101") (pin "2") (pinfunction "PC13_2") (pintype "bidirectional"))
    )
    (net (code "96") (name "unconnected-(IC101A-PC14-Pad3)") (class "Default")
      (node (ref "IC101") (pin "3") (pinfunction "PC14_3") (pintype "bidirectional"))
    )
    (net (code "97") (name "unconnected-(IC302-SPLIT-Pad5)") (class "Default")
      (node (ref "IC302") (pin "5") (pinfunction "SPLIT_5") (pintype "bidirectional"))
    )
    (net (code "98") (name "unconnected-(IC303-R1IN-Pad13)") (class "Default")
      (node (ref "IC303") (pin "13") (pinfunction "R1IN_13") (pintype "input"))
    )
    (net (code "99") (name "unconnected-(IC303-R1OUT-Pad12)") (class "Default")
      (node (ref "IC303") (pin "12") (pinfunction "R1OUT_12") (pintype "output"))
    )
    (net (code "100") (name "unconnected-(IC303-T1IN-Pad11)") (class "Default")
      (node (ref "IC303") (pin "11") (pinfunction "T1IN_11") (pintype "input"))
    )
    (net (code "101") (name "unconnected-(IC303-T1OUT-Pad14)") (class "Default")
      (node (ref "IC303") (pin "14") (pinfunction "T1OUT_14") (pintype "output"))
    )
    (net (code "102") (name "unconnected-(IC304-DB-Pad7)") (class "Default")
      (node (ref "IC304") (pin "7") (pinfunction "DB_7") (pintype "bidirectional"))
    )
    (net (code "103") (name "unconnected-(IC304-DC-Pad9)") (class "Default")
      (node (ref "IC304") (pin "9") (pinfunction "DC_9") (pintype "bidirectional"))
    )
    (net (code "104") (name "unconnected-(IC304-DD-Pad12)") (class "Default")
      (node (ref "IC304") (pin "12") (pinfunction "DD_12") (pintype "bidirectional"))
    )
    (net (code "105") (name "unconnected-(IC304-S1B-Pad5)") (class "Default")
      (node (ref "IC304") (pin "5") (pinfunction "S1B_5") (pintype "bidirectional"))
    )
    (net (code "106") (name "unconnected-(IC304-S1C-Pad11)") (class "Default")
      (node (ref "IC304") (pin "11") (pinfunction "S1C_11") (pintype "bidirectional"))
    )
    (net (code "107") (name "unconnected-(IC304-S1D-Pad14)") (class "Default")
      (node (ref "IC304") (pin "14") (pinfunction "S1D_14") (pintype "bidirectional"))
    )
    (net (code "108") (name "unconnected-(IC304-S2B-Pad6)") (class "Default")
      (node (ref "IC304") (pin "6") (pinfunction "S2B_6") (pintype "bidirectional"))
    )
    (net (code "109") (name "unconnected-(IC304-S2C-Pad10)") (class "Default")
      (node (ref "IC304") (pin "10") (pinfunction "S2C_10") (pintype "bidirectional"))
    )
    (net (code "110") (name "unconnected-(IC304-S2D-Pad13)") (class "Default")
      (node (ref "IC304") (pin "13") (pinfunction "S2D_13") (pintype "bidirectional"))
    )
    (net (code "111") (name "unconnected-(J404-Pad5)") (class "Default")
      (node (ref "J404") (pin "5") (pinfunction "5_5") (pintype "passive"))
    )
    (net (code "112") (name "~{LRF_EN}") (class "Default")
      (node (ref "IC101") (pin "4") (pinfunction "PC15_4") (pintype "bidirectional"))
      (node (ref "J404") (pin "6") (pinfunction "6_6") (pintype "passive"))
      (node (ref "R401") (pin "2") (pinfunction "2_2") (pintype "passive"))
    )
  )
)
